# esquema.net
KiCad netlist of a schematic drawn in EAGLE
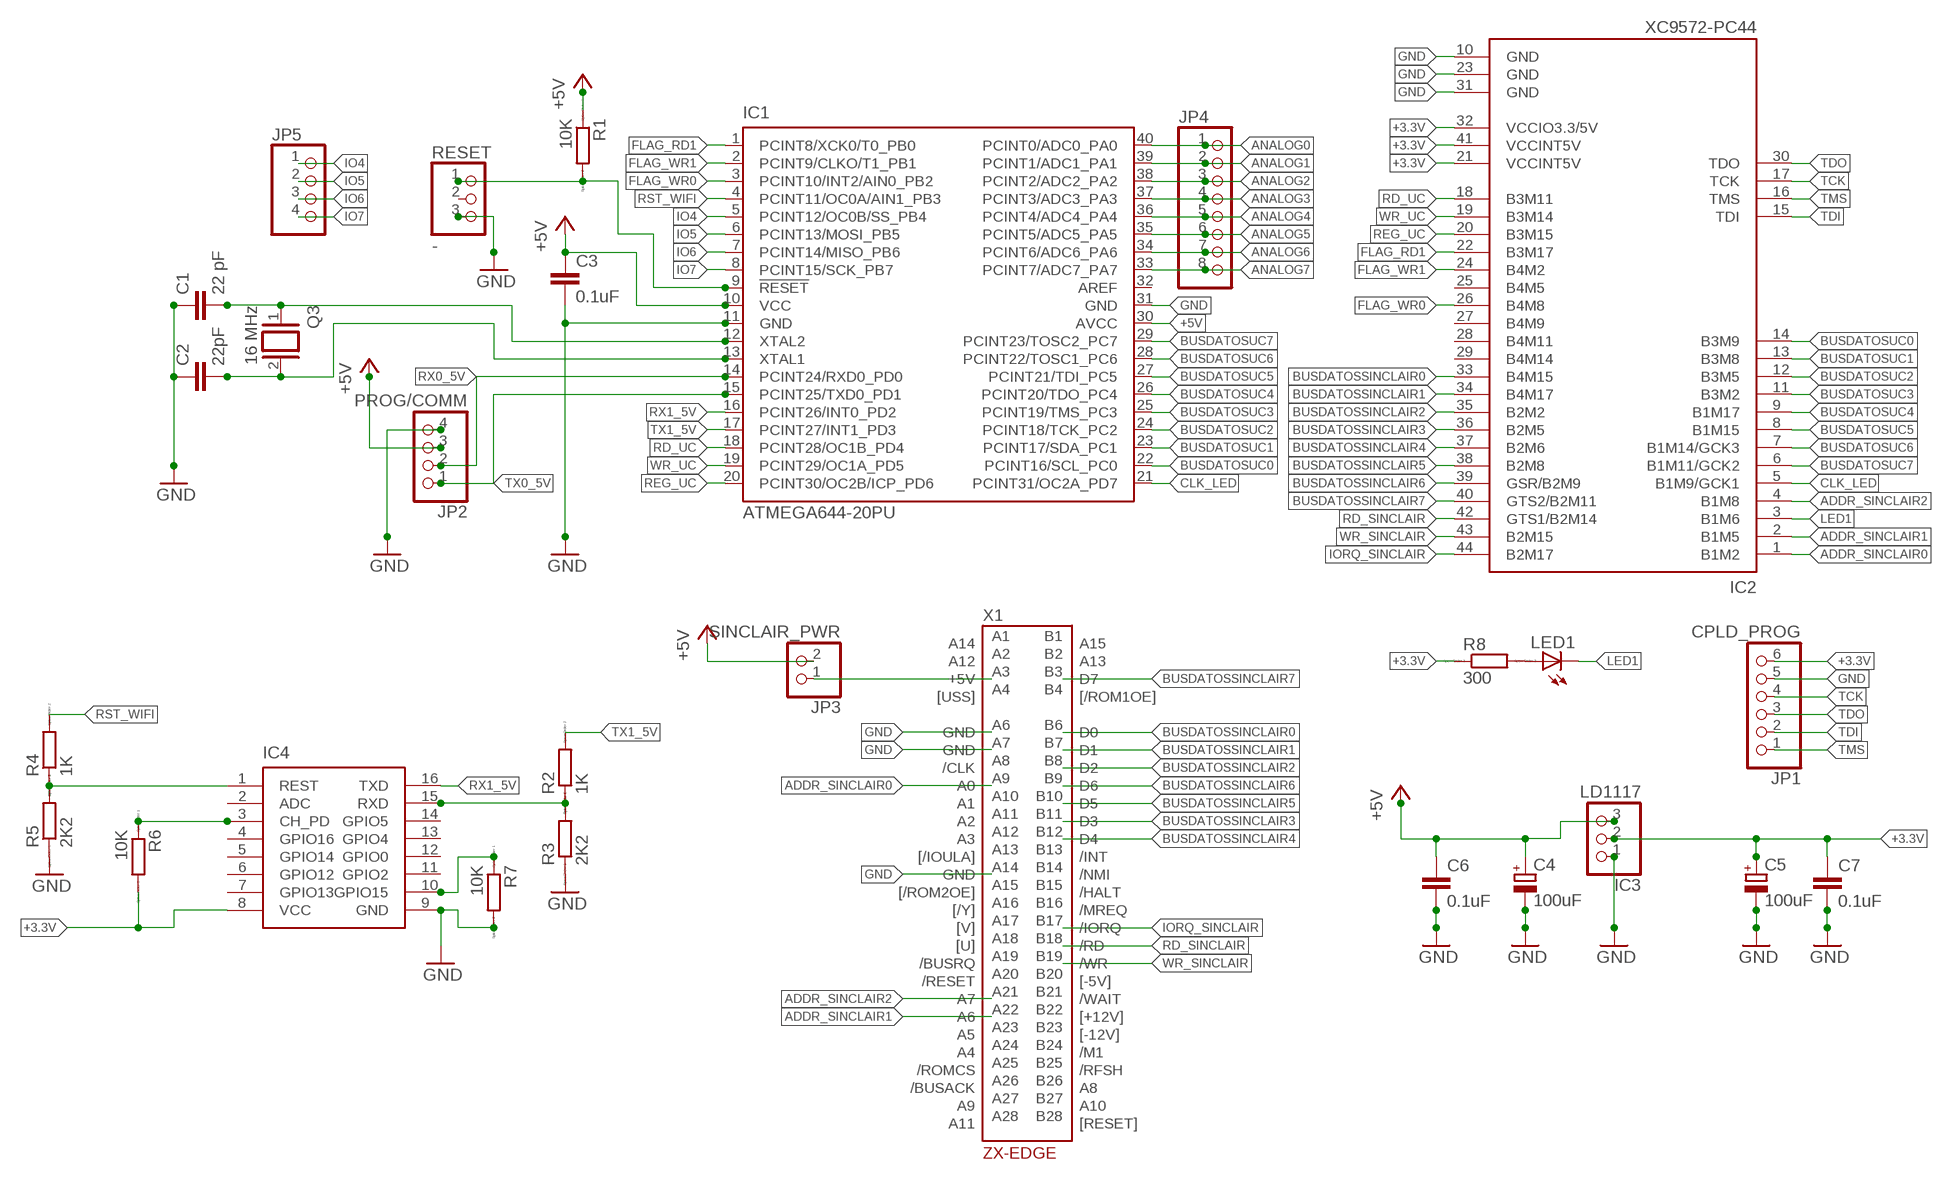
[diagram p0: schematic, sheet 1]

(export (version "E")
  (design (tool "Eeschema 10.0.6"))
  (components
    (comp (ref "C1")
      (value "22 pF")
      (footprint "eagle-import:C025-024X044")
      (libsource (lib "eagle-import") (part "C-EU025-024X044"))
    )
    (comp (ref "C2")
      (value "22pF")
      (footprint "eagle-import:C025-024X044")
      (libsource (lib "eagle-import") (part "C-EU025-024X044"))
    )
    (comp (ref "C3")
      (value "0.1uF")
      (footprint "eagle-import:C025-025X050")
      (libsource (lib "eagle-import") (part "C-EU025-025X050"))
    )
    (comp (ref "C4")
      (value "100uF")
      (footprint "eagle-import:E2,5-7")
      (libsource (lib "eagle-import") (part "CPOL-EUE2.5-7"))
    )
    (comp (ref "C5")
      (value "100uF")
      (footprint "eagle-import:E2,5-7")
      (libsource (lib "eagle-import") (part "CPOL-EUE2.5-7"))
    )
    (comp (ref "C6")
      (value "0.1uF")
      (footprint "eagle-import:C025-025X050")
      (libsource (lib "eagle-import") (part "C-EU025-025X050"))
    )
    (comp (ref "C7")
      (value "0.1uF")
      (footprint "eagle-import:C025-025X050")
      (libsource (lib "eagle-import") (part "C-EU025-025X050"))
    )
    (comp (ref "IC1")
      (value "ATMEGA644-20PU")
      (footprint "eagle-import:DIL40")
      (libsource (lib "eagle-import") (part "ATMEGA644-PU20"))
    )
    (comp (ref "IC2")
      (value "XC9572-PC44")
      (footprint "eagle-import:PLCC-S44")
      (libsource (lib "eagle-import") (part "XC9572-PC44"))
    )
    (comp (ref "IC3")
      (value "LD1117")
      (footprint "eagle-import:1X03")
      (libsource (lib "eagle-import") (part "PINHD-1X3"))
    )
    (comp (ref "IC4")
      (value "ESP-07ESP-07")
      (footprint "eagle-import:ESP-07")
      (libsource (lib "eagle-import") (part "ESP-07ESP-07"))
    )
    (comp (ref "JP1")
      (value "CPLD_PROG")
      (footprint "eagle-import:1X06")
      (libsource (lib "eagle-import") (part "PINHD-1X6"))
    )
    (comp (ref "JP2")
      (value "PROG/COMM")
      (footprint "eagle-import:1X04")
      (libsource (lib "eagle-import") (part "PINHD-1X4"))
    )
    (comp (ref "JP3")
      (value "SINCLAIR_PWR")
      (footprint "eagle-import:1X02")
      (libsource (lib "eagle-import") (part "PINHD-1X2"))
    )
    (comp (ref "JP4")
      (value "PINHD-1X8")
      (footprint "eagle-import:1X08")
      (libsource (lib "eagle-import") (part "PINHD-1X8"))
    )
    (comp (ref "JP5")
      (value "PINHD-1X4")
      (footprint "eagle-import:1X04")
      (libsource (lib "eagle-import") (part "PINHD-1X4"))
    )
    (comp (ref "LED1")
      (value "LED3MM")
      (footprint "eagle-import:LED3MM")
      (libsource (lib "eagle-import") (part "LED3MM"))
    )
    (comp (ref "Q3")
      (value "16 MHz")
      (footprint "eagle-import:QS")
      (libsource (lib "eagle-import") (part "XTAL/S"))
    )
    (comp (ref "R1")
      (value "10K")
      (footprint "eagle-import:0207_10")
      (libsource (lib "eagle-import") (part "R-EU_0207_10"))
    )
    (comp (ref "R2")
      (value "1K")
      (footprint "eagle-import:0207_10")
      (libsource (lib "eagle-import") (part "R-EU_0207_10"))
    )
    (comp (ref "R3")
      (value "2K2")
      (footprint "eagle-import:0207_10")
      (libsource (lib "eagle-import") (part "R-EU_0207_10"))
    )
    (comp (ref "R4")
      (value "1K")
      (footprint "eagle-import:0207_10")
      (libsource (lib "eagle-import") (part "R-EU_0207_10"))
    )
    (comp (ref "R5")
      (value "2K2")
      (footprint "eagle-import:0207_10")
      (libsource (lib "eagle-import") (part "R-EU_0207_10"))
    )
    (comp (ref "R6")
      (value "10K")
      (footprint "eagle-import:0207_10")
      (libsource (lib "eagle-import") (part "R-EU_0207_10"))
    )
    (comp (ref "R7")
      (value "10K")
      (footprint "eagle-import:0207_10")
      (libsource (lib "eagle-import") (part "R-EU_0207_10"))
    )
    (comp (ref "R8")
      (value "300")
      (footprint "eagle-import:0207_10")
      (libsource (lib "eagle-import") (part "R-EU_0207_10"))
    )
    (comp (ref "RESET")
      (value "-")
      (footprint "eagle-import:1X03")
      (libsource (lib "eagle-import") (part "PINHD-1X3"))
    )
    (comp (ref "X1")
      (value "ZX-EDGE")
      (footprint "eagle-import:ZX-IFACE")
      (libsource (lib "eagle-import") (part "ZX-EDGE"))
    )
  )
  (nets
    (net (code "1") (name "+3.3V") (class "Default")
      (node (ref "C5") (pin "+") (pinfunction "+_+") (pintype "passive"))
      (node (ref "C7") (pin "1") (pinfunction "1_1") (pintype "passive"))
      (node (ref "IC2") (pin "21") (pinfunction "VCCINT5V_21") (pintype "bidirectional"))
      (node (ref "IC2") (pin "32") (pinfunction "VCCIO3.3/5V_32") (pintype "bidirectional"))
      (node (ref "IC2") (pin "41") (pinfunction "VCCINT5V_41") (pintype "bidirectional"))
      (node (ref "IC3") (pin "2") (pinfunction "2_2") (pintype "passive"))
      (node (ref "IC4") (pin "8") (pinfunction "VCC_8") (pintype "power_in"))
      (node (ref "JP1") (pin "6") (pinfunction "6_6") (pintype "passive"))
      (node (ref "R6") (pin "2") (pinfunction "2_2") (pintype "passive"))
      (node (ref "R8") (pin "1") (pinfunction "1_1") (pintype "passive"))
    )
    (net (code "2") (name "+5V") (class "Default")
      (node (ref "C3") (pin "1") (pinfunction "1_1") (pintype "passive"))
      (node (ref "C4") (pin "+") (pinfunction "+_+") (pintype "passive"))
      (node (ref "C6") (pin "1") (pinfunction "1_1") (pintype "passive"))
      (node (ref "IC1") (pin "10") (pinfunction "VCC_10") (pintype "power_in"))
      (node (ref "IC1") (pin "30") (pinfunction "AVCC_30") (pintype "power_in"))
      (node (ref "IC3") (pin "3") (pinfunction "3_3") (pintype "passive"))
      (node (ref "JP2") (pin "3") (pinfunction "3_3") (pintype "passive"))
      (node (ref "JP3") (pin "2") (pinfunction "2_2") (pintype "passive"))
      (node (ref "R1") (pin "1") (pinfunction "1_1") (pintype "passive"))
    )
    (net (code "3") (name "ADDR_SINCLAIR0") (class "Default")
      (node (ref "IC2") (pin "1") (pinfunction "B1M2_1") (pintype "bidirectional"))
      (node (ref "X1") (pin "A9") (pinfunction "A0_A9") (pintype "bidirectional"))
    )
    (net (code "4") (name "ADDR_SINCLAIR1") (class "Default")
      (node (ref "IC2") (pin "2") (pinfunction "B1M5_2") (pintype "bidirectional"))
      (node (ref "X1") (pin "A22") (pinfunction "A6_A22") (pintype "bidirectional"))
    )
    (net (code "5") (name "ADDR_SINCLAIR2") (class "Default")
      (node (ref "IC2") (pin "4") (pinfunction "B1M8_4") (pintype "bidirectional"))
      (node (ref "X1") (pin "A21") (pinfunction "A7_A21") (pintype "bidirectional"))
    )
    (net (code "6") (name "ANALOG0") (class "Default")
      (node (ref "IC1") (pin "40") (pinfunction "PCINT0/ADC0_PA0_40") (pintype "bidirectional"))
      (node (ref "JP4") (pin "1") (pinfunction "1_1") (pintype "passive"))
    )
    (net (code "7") (name "ANALOG1") (class "Default")
      (node (ref "IC1") (pin "39") (pinfunction "PCINT1/ADC1_PA1_39") (pintype "bidirectional"))
      (node (ref "JP4") (pin "2") (pinfunction "2_2") (pintype "passive"))
    )
    (net (code "8") (name "ANALOG2") (class "Default")
      (node (ref "IC1") (pin "38") (pinfunction "PCINT2/ADC2_PA2_38") (pintype "bidirectional"))
      (node (ref "JP4") (pin "3") (pinfunction "3_3") (pintype "passive"))
    )
    (net (code "9") (name "ANALOG3") (class "Default")
      (node (ref "IC1") (pin "37") (pinfunction "PCINT3/ADC3_PA3_37") (pintype "bidirectional"))
      (node (ref "JP4") (pin "4") (pinfunction "4_4") (pintype "passive"))
    )
    (net (code "10") (name "ANALOG4") (class "Default")
      (node (ref "IC1") (pin "36") (pinfunction "PCINT4/ADC4_PA4_36") (pintype "bidirectional"))
      (node (ref "JP4") (pin "5") (pinfunction "5_5") (pintype "passive"))
    )
    (net (code "11") (name "ANALOG5") (class "Default")
      (node (ref "IC1") (pin "35") (pinfunction "PCINT5/ADC5_PA5_35") (pintype "bidirectional"))
      (node (ref "JP4") (pin "6") (pinfunction "6_6") (pintype "passive"))
    )
    (net (code "12") (name "ANALOG6") (class "Default")
      (node (ref "IC1") (pin "34") (pinfunction "PCINT6/ADC6_PA6_34") (pintype "bidirectional"))
      (node (ref "JP4") (pin "7") (pinfunction "7_7") (pintype "passive"))
    )
    (net (code "13") (name "ANALOG7") (class "Default")
      (node (ref "IC1") (pin "33") (pinfunction "PCINT7/ADC7_PA7_33") (pintype "bidirectional"))
      (node (ref "JP4") (pin "8") (pinfunction "8_8") (pintype "passive"))
    )
    (net (code "14") (name "BUSDATOSSINCLAIR0") (class "Default")
      (node (ref "IC2") (pin "33") (pinfunction "B4M15_33") (pintype "bidirectional"))
      (node (ref "X1") (pin "B6") (pinfunction "D0_B6") (pintype "bidirectional"))
    )
    (net (code "15") (name "BUSDATOSSINCLAIR1") (class "Default")
      (node (ref "IC2") (pin "34") (pinfunction "B4M17_34") (pintype "bidirectional"))
      (node (ref "X1") (pin "B7") (pinfunction "D1_B7") (pintype "bidirectional"))
    )
    (net (code "16") (name "BUSDATOSSINCLAIR2") (class "Default")
      (node (ref "IC2") (pin "35") (pinfunction "B2M2_35") (pintype "bidirectional"))
      (node (ref "X1") (pin "B8") (pinfunction "D2_B8") (pintype "bidirectional"))
    )
    (net (code "17") (name "BUSDATOSSINCLAIR3") (class "Default")
      (node (ref "IC2") (pin "36") (pinfunction "B2M5_36") (pintype "bidirectional"))
      (node (ref "X1") (pin "B11") (pinfunction "D3_B11") (pintype "bidirectional"))
    )
    (net (code "18") (name "BUSDATOSSINCLAIR4") (class "Default")
      (node (ref "IC2") (pin "37") (pinfunction "B2M6_37") (pintype "bidirectional"))
      (node (ref "X1") (pin "B12") (pinfunction "D4_B12") (pintype "bidirectional"))
    )
    (net (code "19") (name "BUSDATOSSINCLAIR5") (class "Default")
      (node (ref "IC2") (pin "38") (pinfunction "B2M8_38") (pintype "bidirectional"))
      (node (ref "X1") (pin "B10") (pinfunction "D5_B10") (pintype "bidirectional"))
    )
    (net (code "20") (name "BUSDATOSSINCLAIR6") (class "Default")
      (node (ref "IC2") (pin "39") (pinfunction "GSR/B2M9_39") (pintype "bidirectional"))
      (node (ref "X1") (pin "B9") (pinfunction "D6_B9") (pintype "bidirectional"))
    )
    (net (code "21") (name "BUSDATOSSINCLAIR7") (class "Default")
      (node (ref "IC2") (pin "40") (pinfunction "GTS2/B2M11_40") (pintype "bidirectional"))
      (node (ref "X1") (pin "B3") (pinfunction "D7_B3") (pintype "bidirectional"))
    )
    (net (code "22") (name "BUSDATOSUC0") (class "Default")
      (node (ref "IC1") (pin "22") (pinfunction "PCINT16/SCL_PC0_22") (pintype "bidirectional"))
      (node (ref "IC2") (pin "14") (pinfunction "B3M9_14") (pintype "bidirectional"))
    )
    (net (code "23") (name "BUSDATOSUC1") (class "Default")
      (node (ref "IC1") (pin "23") (pinfunction "PCINT17/SDA_PC1_23") (pintype "bidirectional"))
      (node (ref "IC2") (pin "13") (pinfunction "B3M8_13") (pintype "bidirectional"))
    )
    (net (code "24") (name "BUSDATOSUC2") (class "Default")
      (node (ref "IC1") (pin "24") (pinfunction "PCINT18/TCK_PC2_24") (pintype "bidirectional"))
      (node (ref "IC2") (pin "12") (pinfunction "B3M5_12") (pintype "bidirectional"))
    )
    (net (code "25") (name "BUSDATOSUC3") (class "Default")
      (node (ref "IC1") (pin "25") (pinfunction "PCINT19/TMS_PC3_25") (pintype "bidirectional"))
      (node (ref "IC2") (pin "11") (pinfunction "B3M2_11") (pintype "bidirectional"))
    )
    (net (code "26") (name "BUSDATOSUC4") (class "Default")
      (node (ref "IC1") (pin "26") (pinfunction "PCINT20/TDO_PC4_26") (pintype "bidirectional"))
      (node (ref "IC2") (pin "9") (pinfunction "B1M17_9") (pintype "bidirectional"))
    )
    (net (code "27") (name "BUSDATOSUC5") (class "Default")
      (node (ref "IC1") (pin "27") (pinfunction "PCINT21/TDI_PC5_27") (pintype "bidirectional"))
      (node (ref "IC2") (pin "8") (pinfunction "B1M15_8") (pintype "bidirectional"))
    )
    (net (code "28") (name "BUSDATOSUC6") (class "Default")
      (node (ref "IC1") (pin "28") (pinfunction "PCINT22/TOSC1_PC6_28") (pintype "bidirectional"))
      (node (ref "IC2") (pin "7") (pinfunction "B1M14/GCK3_7") (pintype "bidirectional"))
    )
    (net (code "29") (name "BUSDATOSUC7") (class "Default")
      (node (ref "IC1") (pin "29") (pinfunction "PCINT23/TOSC2_PC7_29") (pintype "bidirectional"))
      (node (ref "IC2") (pin "6") (pinfunction "B1M11/GCK2_6") (pintype "bidirectional"))
    )
    (net (code "30") (name "CLK_LED") (class "Default")
      (node (ref "IC1") (pin "21") (pinfunction "PCINT31/OC2A_PD7_21") (pintype "bidirectional"))
      (node (ref "IC2") (pin "5") (pinfunction "B1M9/GCK1_5") (pintype "bidirectional"))
    )
    (net (code "31") (name "FLAG_RD1") (class "Default")
      (node (ref "IC1") (pin "1") (pinfunction "PCINT8/XCK0/T0_PB0_1") (pintype "bidirectional"))
      (node (ref "IC2") (pin "22") (pinfunction "B3M17_22") (pintype "bidirectional"))
    )
    (net (code "32") (name "FLAG_WR0") (class "Default")
      (node (ref "IC1") (pin "3") (pinfunction "PCINT10/INT2/AIN0_PB2_3") (pintype "bidirectional"))
      (node (ref "IC2") (pin "26") (pinfunction "B4M8_26") (pintype "bidirectional"))
    )
    (net (code "33") (name "FLAG_WR1") (class "Default")
      (node (ref "IC1") (pin "2") (pinfunction "PCINT9/CLKO/T1_PB1_2") (pintype "bidirectional"))
      (node (ref "IC2") (pin "24") (pinfunction "B4M2_24") (pintype "bidirectional"))
    )
    (net (code "34") (name "GND") (class "Default")
      (node (ref "C1") (pin "1") (pinfunction "1_1") (pintype "passive"))
      (node (ref "C2") (pin "1") (pinfunction "1_1") (pintype "passive"))
      (node (ref "C3") (pin "2") (pinfunction "2_2") (pintype "passive"))
      (node (ref "C4") (pin "-") (pinfunction "-_-") (pintype "passive"))
      (node (ref "C5") (pin "-") (pinfunction "-_-") (pintype "passive"))
      (node (ref "C6") (pin "2") (pinfunction "2_2") (pintype "passive"))
      (node (ref "C7") (pin "2") (pinfunction "2_2") (pintype "passive"))
      (node (ref "IC1") (pin "11") (pinfunction "GND_11") (pintype "power_in"))
      (node (ref "IC1") (pin "31") (pinfunction "GND_31") (pintype "power_in"))
      (node (ref "IC2") (pin "10") (pinfunction "GND_10") (pintype "bidirectional"))
      (node (ref "IC2") (pin "23") (pinfunction "GND_23") (pintype "bidirectional"))
      (node (ref "IC2") (pin "31") (pinfunction "GND_31") (pintype "bidirectional"))
      (node (ref "IC3") (pin "1") (pinfunction "1_1") (pintype "passive"))
      (node (ref "IC4") (pin "9") (pinfunction "GND_9") (pintype "power_in"))
      (node (ref "JP1") (pin "5") (pinfunction "5_5") (pintype "passive"))
      (node (ref "JP2") (pin "4") (pinfunction "4_4") (pintype "passive"))
      (node (ref "R3") (pin "1") (pinfunction "1_1") (pintype "passive"))
      (node (ref "R5") (pin "1") (pinfunction "1_1") (pintype "passive"))
      (node (ref "R7") (pin "2") (pinfunction "2_2") (pintype "passive"))
      (node (ref "RESET") (pin "3") (pinfunction "3_3") (pintype "passive"))
      (node (ref "X1") (pin "A14") (pinfunction "GND_A14") (pintype "bidirectional"))
      (node (ref "X1") (pin "A6") (pinfunction "GND_A6") (pintype "bidirectional"))
      (node (ref "X1") (pin "A7") (pinfunction "GND_A7") (pintype "bidirectional"))
    )
    (net (code "35") (name "IO4") (class "Default")
      (node (ref "IC1") (pin "5") (pinfunction "PCINT12/OC0B/SS_PB4_5") (pintype "bidirectional"))
      (node (ref "JP5") (pin "1") (pinfunction "1_1") (pintype "passive"))
    )
    (net (code "36") (name "IO5") (class "Default")
      (node (ref "IC1") (pin "6") (pinfunction "PCINT13/MOSI_PB5_6") (pintype "bidirectional"))
      (node (ref "JP5") (pin "2") (pinfunction "2_2") (pintype "passive"))
    )
    (net (code "37") (name "IO6") (class "Default")
      (node (ref "IC1") (pin "7") (pinfunction "PCINT14/MISO_PB6_7") (pintype "bidirectional"))
      (node (ref "JP5") (pin "3") (pinfunction "3_3") (pintype "passive"))
    )
    (net (code "38") (name "IO7") (class "Default")
      (node (ref "IC1") (pin "8") (pinfunction "PCINT15/SCK_PB7_8") (pintype "bidirectional"))
      (node (ref "JP5") (pin "4") (pinfunction "4_4") (pintype "passive"))
    )
    (net (code "39") (name "IORQ_SINCLAIR") (class "Default")
      (node (ref "IC2") (pin "44") (pinfunction "B2M17_44") (pintype "bidirectional"))
      (node (ref "X1") (pin "B17") (pinfunction "/IORQ_B17") (pintype "bidirectional"))
    )
    (net (code "40") (name "LED1") (class "Default")
      (node (ref "IC2") (pin "3") (pinfunction "B1M6_3") (pintype "bidirectional"))
      (node (ref "LED1") (pin "K") (pinfunction "C_K") (pintype "passive"))
    )
    (net (code "41") (name "Net-(IC1-XTAL1)") (class "Default")
      (node (ref "C2") (pin "2") (pinfunction "2_2") (pintype "passive"))
      (node (ref "IC1") (pin "13") (pinfunction "XTAL1_13") (pintype "input"))
      (node (ref "Q3") (pin "2") (pinfunction "2_2") (pintype "passive"))
    )
    (net (code "42") (name "Net-(IC1-XTAL2)") (class "Default")
      (node (ref "C1") (pin "2") (pinfunction "2_2") (pintype "passive"))
      (node (ref "IC1") (pin "12") (pinfunction "XTAL2_12") (pintype "output"))
      (node (ref "Q3") (pin "1") (pinfunction "1_1") (pintype "passive"))
    )
    (net (code "43") (name "Net-(IC1-~{RESET})") (class "Default")
      (node (ref "IC1") (pin "9") (pinfunction "~{RESET}_9") (pintype "input"))
      (node (ref "R1") (pin "2") (pinfunction "2_2") (pintype "passive"))
      (node (ref "RESET") (pin "1") (pinfunction "1_1") (pintype "passive"))
    )
    (net (code "44") (name "Net-(IC4-CH_PD)") (class "Default")
      (node (ref "IC4") (pin "3") (pinfunction "CH_PD_3") (pintype "bidirectional"))
      (node (ref "R6") (pin "1") (pinfunction "1_1") (pintype "passive"))
    )
    (net (code "45") (name "Net-(IC4-GPIO15)") (class "Default")
      (node (ref "IC4") (pin "10") (pinfunction "GPIO15_10") (pintype "bidirectional"))
      (node (ref "R7") (pin "1") (pinfunction "1_1") (pintype "passive"))
    )
    (net (code "46") (name "Net-(IC4-REST)") (class "Default")
      (node (ref "IC4") (pin "1") (pinfunction "REST_1") (pintype "input"))
      (node (ref "R4") (pin "1") (pinfunction "1_1") (pintype "passive"))
      (node (ref "R5") (pin "2") (pinfunction "2_2") (pintype "passive"))
    )
    (net (code "47") (name "Net-(IC4-RXD)") (class "Default")
      (node (ref "IC4") (pin "15") (pinfunction "RXD_15") (pintype "input"))
      (node (ref "R2") (pin "1") (pinfunction "1_1") (pintype "passive"))
      (node (ref "R3") (pin "2") (pinfunction "2_2") (pintype "passive"))
    )
    (net (code "48") (name "Net-(LED1-PadA)") (class "Default")
      (node (ref "LED1") (pin "A") (pinfunction "A_A") (pintype "passive"))
      (node (ref "R8") (pin "2") (pinfunction "2_2") (pintype "passive"))
    )
    (net (code "49") (name "Net-(X1-+5V)") (class "Default")
      (node (ref "JP3") (pin "1") (pinfunction "1_1") (pintype "passive"))
      (node (ref "X1") (pin "A3") (pinfunction "+5V_A3") (pintype "bidirectional"))
    )
    (net (code "50") (name "RD_SINCLAIR") (class "Default")
      (node (ref "IC2") (pin "42") (pinfunction "GTS1/B2M14_42") (pintype "bidirectional"))
      (node (ref "X1") (pin "B18") (pinfunction "/RD_B18") (pintype "bidirectional"))
    )
    (net (code "51") (name "RD_UC") (class "Default")
      (node (ref "IC1") (pin "18") (pinfunction "PCINT28/OC1B_PD4_18") (pintype "bidirectional"))
      (node (ref "IC2") (pin "18") (pinfunction "B3M11_18") (pintype "bidirectional"))
    )
    (net (code "52") (name "REG_UC") (class "Default")
      (node (ref "IC1") (pin "20") (pinfunction "PCINT30/OC2B/ICP_PD6_20") (pintype "bidirectional"))
      (node (ref "IC2") (pin "20") (pinfunction "B3M15_20") (pintype "bidirectional"))
    )
    (net (code "53") (name "RST_WIFI") (class "Default")
      (node (ref "IC1") (pin "4") (pinfunction "PCINT11/OC0A/AIN1_PB3_4") (pintype "bidirectional"))
      (node (ref "R4") (pin "2") (pinfunction "2_2") (pintype "passive"))
    )
    (net (code "54") (name "RX0_5V") (class "Default")
      (node (ref "IC1") (pin "14") (pinfunction "PCINT24/RXD0_PD0_14") (pintype "bidirectional"))
      (node (ref "JP2") (pin "2") (pinfunction "2_2") (pintype "passive"))
    )
    (net (code "55") (name "RX1_5V") (class "Default")
      (node (ref "IC1") (pin "16") (pinfunction "PCINT26/INT0_PD2_16") (pintype "bidirectional"))
      (node (ref "IC4") (pin "16") (pinfunction "TXD_16") (pintype "output"))
    )
    (net (code "56") (name "TCK") (class "Default")
      (node (ref "IC2") (pin "17") (pinfunction "TCK_17") (pintype "bidirectional"))
      (node (ref "JP1") (pin "4") (pinfunction "4_4") (pintype "passive"))
    )
    (net (code "57") (name "TDI") (class "Default")
      (node (ref "IC2") (pin "15") (pinfunction "TDI_15") (pintype "bidirectional"))
      (node (ref "JP1") (pin "2") (pinfunction "2_2") (pintype "passive"))
    )
    (net (code "58") (name "TDO") (class "Default")
      (node (ref "IC2") (pin "30") (pinfunction "TDO_30") (pintype "bidirectional"))
      (node (ref "JP1") (pin "3") (pinfunction "3_3") (pintype "passive"))
    )
    (net (code "59") (name "TMS") (class "Default")
      (node (ref "IC2") (pin "16") (pinfunction "TMS_16") (pintype "bidirectional"))
      (node (ref "JP1") (pin "1") (pinfunction "1_1") (pintype "passive"))
    )
    (net (code "60") (name "TX0_5V") (class "Default")
      (node (ref "IC1") (pin "15") (pinfunction "PCINT25/TXD0_PD1_15") (pintype "bidirectional"))
      (node (ref "JP2") (pin "1") (pinfunction "1_1") (pintype "passive"))
    )
    (net (code "61") (name "TX1_5V") (class "Default")
      (node (ref "IC1") (pin "17") (pinfunction "PCINT27/INT1_PD3_17") (pintype "bidirectional"))
      (node (ref "R2") (pin "2") (pinfunction "2_2") (pintype "passive"))
    )
    (net (code "62") (name "WR_SINCLAIR") (class "Default")
      (node (ref "IC2") (pin "43") (pinfunction "B2M15_43") (pintype "bidirectional"))
      (node (ref "X1") (pin "B19") (pinfunction "/WR_B19") (pintype "bidirectional"))
    )
    (net (code "63") (name "WR_UC") (class "Default")
      (node (ref "IC1") (pin "19") (pinfunction "PCINT29/OC1A_PD5_19") (pintype "bidirectional"))
      (node (ref "IC2") (pin "19") (pinfunction "B3M14_19") (pintype "bidirectional"))
    )
    (net (code "64") (name "unconnected-(IC1-AREF-Pad32)") (class "Default")
      (node (ref "IC1") (pin "32") (pinfunction "AREF_32") (pintype "passive"))
    )
    (net (code "65") (name "unconnected-(IC2-B4M5-Pad25)") (class "Default")
      (node (ref "IC2") (pin "25") (pinfunction "B4M5_25") (pintype "bidirectional"))
    )
    (net (code "66") (name "unconnected-(IC2-B4M9-Pad27)") (class "Default")
      (node (ref "IC2") (pin "27") (pinfunction "B4M9_27") (pintype "bidirectional"))
    )
    (net (code "67") (name "unconnected-(IC2-B4M11-Pad28)") (class "Default")
      (node (ref "IC2") (pin "28") (pinfunction "B4M11_28") (pintype "bidirectional"))
    )
    (net (code "68") (name "unconnected-(IC2-B4M14-Pad29)") (class "Default")
      (node (ref "IC2") (pin "29") (pinfunction "B4M14_29") (pintype "bidirectional"))
    )
    (net (code "69") (name "unconnected-(IC4-ADC-Pad2)") (class "Default")
      (node (ref "IC4") (pin "2") (pinfunction "ADC_2") (pintype "bidirectional"))
    )
    (net (code "70") (name "unconnected-(IC4-GPIO0-Pad12)") (class "Default")
      (node (ref "IC4") (pin "12") (pinfunction "GPIO0_12") (pintype "bidirectional"))
    )
    (net (code "71") (name "unconnected-(IC4-GPIO2-Pad11)") (class "Default")
      (node (ref "IC4") (pin "11") (pinfunction "GPIO2_11") (pintype "bidirectional"))
    )
    (net (code "72") (name "unconnected-(IC4-GPIO4-Pad13)") (class "Default")
      (node (ref "IC4") (pin "13") (pinfunction "GPIO4_13") (pintype "bidirectional"))
    )
    (net (code "73") (name "unconnected-(IC4-GPIO5-Pad14)") (class "Default")
      (node (ref "IC4") (pin "14") (pinfunction "GPIO5_14") (pintype "bidirectional"))
    )
    (net (code "74") (name "unconnected-(IC4-GPIO12-Pad6)") (class "Default")
      (node (ref "IC4") (pin "6") (pinfunction "GPIO12_6") (pintype "bidirectional"))
    )
    (net (code "75") (name "unconnected-(IC4-GPIO13-Pad7)") (class "Default")
      (node (ref "IC4") (pin "7") (pinfunction "GPIO13_7") (pintype "bidirectional"))
    )
    (net (code "76") (name "unconnected-(IC4-GPIO14-Pad5)") (class "Default")
      (node (ref "IC4") (pin "5") (pinfunction "GPIO14_5") (pintype "bidirectional"))
    )
    (net (code "77") (name "unconnected-(IC4-GPIO16-Pad4)") (class "Default")
      (node (ref "IC4") (pin "4") (pinfunction "GPIO16_4") (pintype "bidirectional"))
    )
    (net (code "78") (name "unconnected-(RESET-Pad2)") (class "Default")
      (node (ref "RESET") (pin "2") (pinfunction "2_2") (pintype "passive"))
    )
    (net (code "79") (name "unconnected-(X1-A1-PadA10)") (class "Default")
      (node (ref "X1") (pin "A10") (pinfunction "A1_A10") (pintype "bidirectional"))
    )
    (net (code "80") (name "unconnected-(X1-A2-PadA11)") (class "Default")
      (node (ref "X1") (pin "A11") (pinfunction "A2_A11") (pintype "bidirectional"))
    )
    (net (code "81") (name "unconnected-(X1-A3-PadA12)") (class "Default")
      (node (ref "X1") (pin "A12") (pinfunction "A3_A12") (pintype "bidirectional"))
    )
    (net (code "82") (name "unconnected-(X1-A4-PadA24)") (class "Default")
      (node (ref "X1") (pin "A24") (pinfunction "A4_A24") (pintype "bidirectional"))
    )
    (net (code "83") (name "unconnected-(X1-A5-PadA23)") (class "Default")
      (node (ref "X1") (pin "A23") (pinfunction "A5_A23") (pintype "bidirectional"))
    )
    (net (code "84") (name "unconnected-(X1-A8-PadB26)") (class "Default")
      (node (ref "X1") (pin "B26") (pinfunction "A8_B26") (pintype "bidirectional"))
    )
    (net (code "85") (name "unconnected-(X1-A9-PadA27)") (class "Default")
      (node (ref "X1") (pin "A27") (pinfunction "A9_A27") (pintype "bidirectional"))
    )
    (net (code "86") (name "unconnected-(X1-A10-PadB27)") (class "Default")
      (node (ref "X1") (pin "B27") (pinfunction "A10_B27") (pintype "bidirectional"))
    )
    (net (code "87") (name "unconnected-(X1-A11-PadA28)") (class "Default")
      (node (ref "X1") (pin "A28") (pinfunction "A11_A28") (pintype "bidirectional"))
    )
    (net (code "88") (name "unconnected-(X1-A12-PadA2)") (class "Default")
      (node (ref "X1") (pin "A2") (pinfunction "A12_A2") (pintype "bidirectional"))
    )
    (net (code "89") (name "unconnected-(X1-A13-PadB2)") (class "Default")
      (node (ref "X1") (pin "B2") (pinfunction "A13_B2") (pintype "bidirectional"))
    )
    (net (code "90") (name "unconnected-(X1-A14-PadA1)") (class "Default")
      (node (ref "X1") (pin "A1") (pinfunction "A14_A1") (pintype "bidirectional"))
    )
    (net (code "91") (name "unconnected-(X1-A15-PadB1)") (class "Default")
      (node (ref "X1") (pin "B1") (pinfunction "A15_B1") (pintype "bidirectional"))
    )
    (net (code "92") (name "unconnected-(X1-[+12V]-PadB22)") (class "Default")
      (node (ref "X1") (pin "B22") (pinfunction "[+12V]_B22") (pintype "bidirectional"))
    )
    (net (code "93") (name "unconnected-(X1-[-5V]-PadB20)") (class "Default")
      (node (ref "X1") (pin "B20") (pinfunction "[-5V]_B20") (pintype "bidirectional"))
    )
    (net (code "94") (name "unconnected-(X1-[-12V]-PadB23)") (class "Default")
      (node (ref "X1") (pin "B23") (pinfunction "[-12V]_B23") (pintype "bidirectional"))
    )
    (net (code "95") (name "unconnected-(X1-[RESET]-PadB28)") (class "Default")
      (node (ref "X1") (pin "B28") (pinfunction "[RESET]_B28") (pintype "bidirectional"))
    )
    (net (code "96") (name "unconnected-(X1-[USS]-PadA4)") (class "Default")
      (node (ref "X1") (pin "A4") (pinfunction "[USS]_A4") (pintype "bidirectional"))
    )
    (net (code "97") (name "unconnected-(X1-[U]-PadA18)") (class "Default")
      (node (ref "X1") (pin "A18") (pinfunction "[U]_A18") (pintype "bidirectional"))
    )
    (net (code "98") (name "unconnected-(X1-[V]-PadA17)") (class "Default")
      (node (ref "X1") (pin "A17") (pinfunction "[V]_A17") (pintype "bidirectional"))
    )
    (net (code "99") (name "unconnected-(X1-[{slash}IOULA]-PadA13)") (class "Default")
      (node (ref "X1") (pin "A13") (pinfunction "[/IOULA]_A13") (pintype "bidirectional"))
    )
    (net (code "100") (name "unconnected-(X1-[{slash}ROM1OE]-PadB4)") (class "Default")
      (node (ref "X1") (pin "B4") (pinfunction "[/ROM1OE]_B4") (pintype "bidirectional"))
    )
    (net (code "101") (name "unconnected-(X1-[{slash}ROM2OE]-PadA15)") (class "Default")
      (node (ref "X1") (pin "A15") (pinfunction "[/ROM2OE]_A15") (pintype "bidirectional"))
    )
    (net (code "102") (name "unconnected-(X1-[{slash}Y]-PadA16)") (class "Default")
      (node (ref "X1") (pin "A16") (pinfunction "[/Y]_A16") (pintype "bidirectional"))
    )
    (net (code "103") (name "unconnected-(X1-{slash}BUSACK-PadA26)") (class "Default")
      (node (ref "X1") (pin "A26") (pinfunction "/BUSACK_A26") (pintype "bidirectional"))
    )
    (net (code "104") (name "unconnected-(X1-{slash}BUSRQ-PadA19)") (class "Default")
      (node (ref "X1") (pin "A19") (pinfunction "/BUSRQ_A19") (pintype "bidirectional"))
    )
    (net (code "105") (name "unconnected-(X1-{slash}CLK-PadA8)") (class "Default")
      (node (ref "X1") (pin "A8") (pinfunction "/CLK_A8") (pintype "bidirectional"))
    )
    (net (code "106") (name "unconnected-(X1-{slash}HALT-PadB15)") (class "Default")
      (node (ref "X1") (pin "B15") (pinfunction "/HALT_B15") (pintype "bidirectional"))
    )
    (net (code "107") (name "unconnected-(X1-{slash}INT-PadB13)") (class "Default")
      (node (ref "X1") (pin "B13") (pinfunction "/INT_B13") (pintype "bidirectional"))
    )
    (net (code "108") (name "unconnected-(X1-{slash}M1-PadB24)") (class "Default")
      (node (ref "X1") (pin "B24") (pinfunction "/M1_B24") (pintype "bidirectional"))
    )
    (net (code "109") (name "unconnected-(X1-{slash}MREQ-PadB16)") (class "Default")
      (node (ref "X1") (pin "B16") (pinfunction "/MREQ_B16") (pintype "bidirectional"))
    )
    (net (code "110") (name "unconnected-(X1-{slash}NMI-PadB14)") (class "Default")
      (node (ref "X1") (pin "B14") (pinfunction "/NMI_B14") (pintype "bidirectional"))
    )
    (net (code "111") (name "unconnected-(X1-{slash}RESET-PadA20)") (class "Default")
      (node (ref "X1") (pin "A20") (pinfunction "/RESET_A20") (pintype "bidirectional"))
    )
    (net (code "112") (name "unconnected-(X1-{slash}RFSH-PadB25)") (class "Default")
      (node (ref "X1") (pin "B25") (pinfunction "/RFSH_B25") (pintype "bidirectional"))
    )
    (net (code "113") (name "unconnected-(X1-{slash}ROMCS-PadA25)") (class "Default")
      (node (ref "X1") (pin "A25") (pinfunction "/ROMCS_A25") (pintype "bidirectional"))
    )
    (net (code "114") (name "unconnected-(X1-{slash}WAIT-PadB21)") (class "Default")
      (node (ref "X1") (pin "B21") (pinfunction "/WAIT_B21") (pintype "bidirectional"))
    )
  )
)
